# VoltageRegulator.net
KiCad netlist of a schematic drawn in Altium Designer
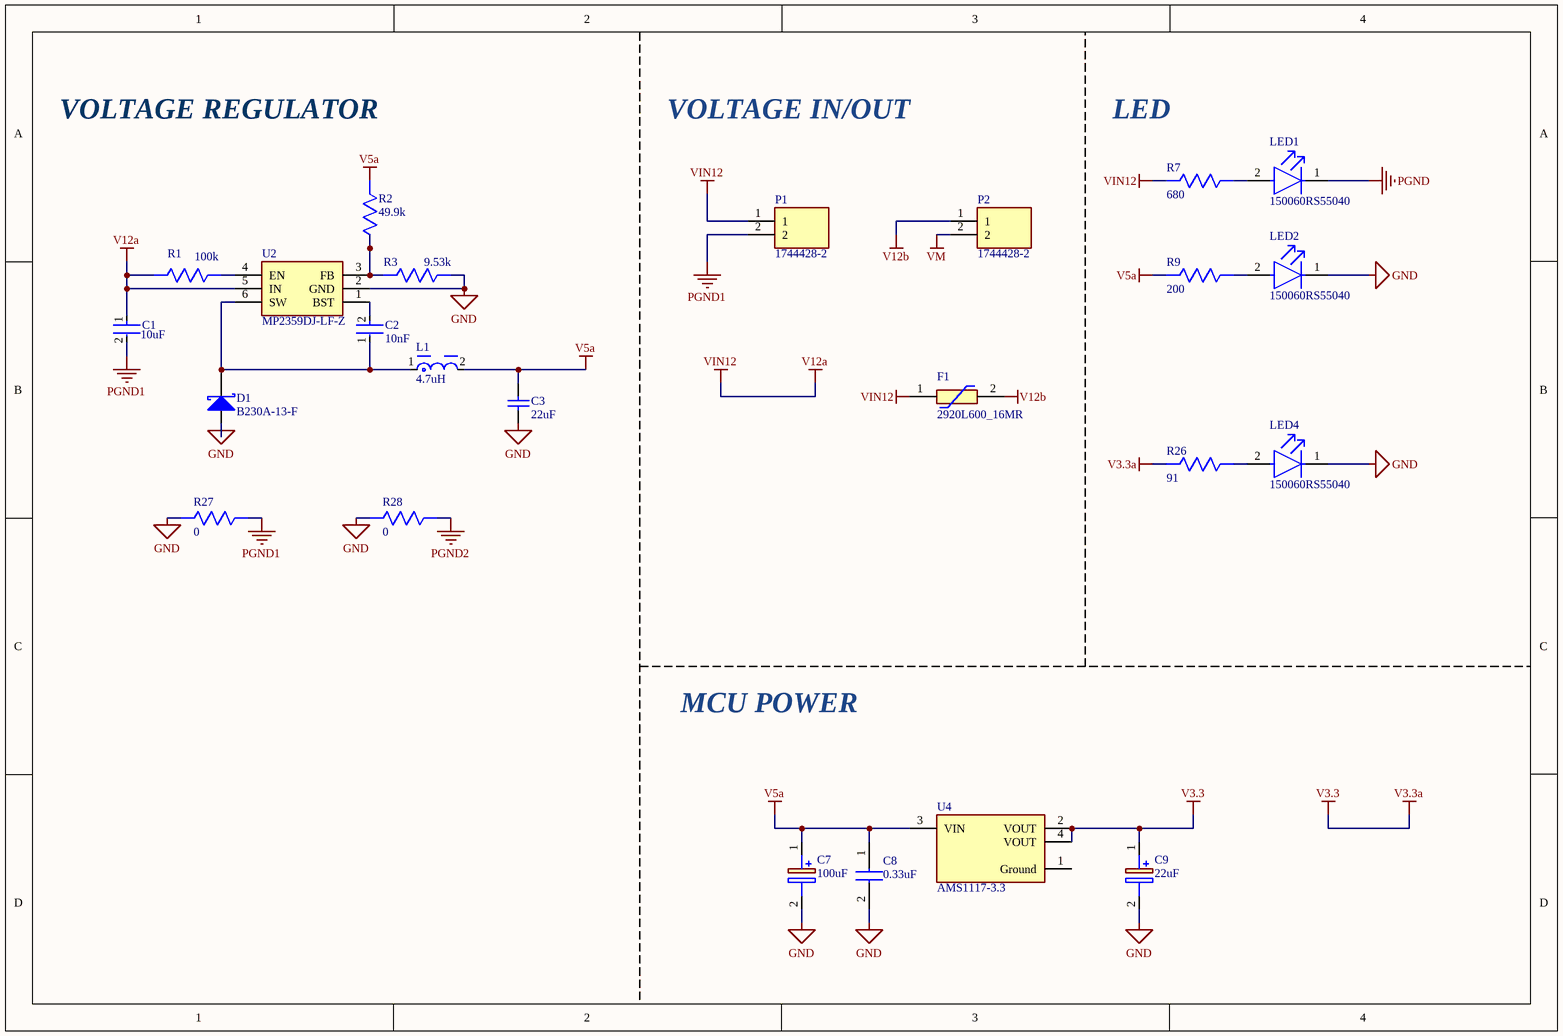
[diagram p0: VoltageRegulator.SchDoc]

(export (version "E")
  (design (tool "Eeschema 10.0.6"))
  (components
    (comp (ref "C1")
      (value "10uF")
      (footprint "FP-C1608-080-IPC_A")
      (description "CAP CER 10UF 25V X5R 0603")
      (fields (field (name "TOLERANCE") "20%"))
      (libsource (lib "Altium Content Vault") (part "11868f565c42a9108669ba33697ecf6"))
    )
    (comp (ref "C2")
      (value "10nF")
      (footprint "FP-C1608-080-0_1-MFG")
      (description "Multilayer Ceramic Capacitors 10nF ±20% 50V X5R SMD 0603")
      (fields (field (name "TOLERANCE") "20%"))
      (libsource (lib "Altium Content Vault") (part "236180d848d6139a670b325ea6854c9"))
    )
    (comp (ref "C3")
      (value "22uF")
      (footprint "CAPC1608X100X20ML10")
      (description "Chip Capacitor, 22 uF, +/- 20%, 10 V, -55 to 85 degC, 0603 (1608 Metric), RoHS, Tape and Reel")
      (fields (field (name "MANUFACTURER") "TDK") (field (name "TOLERANCE") "±20%"))
      (libsource (lib "Altium Content Vault") (part "CAP-NP-2"))
    )
    (comp (ref "C7")
      (value "100uF")
      (footprint "SamacSys:T495E")
      (description "Capacitor Polarised")
      (fields
        (field (name "MANUFACTURER_PART_NUMBER") "T495E107K025ATE100")
        (field (name "MOUSER PART NUMBER") "80-T495E107K025")
      )
      (libsource (lib "*") (part "T495E107K025ATE100"))
    )
    (comp (ref "C8")
      (value "0.33uF")
      (footprint "SamacSys:C1608_Commercial")
      (description "Capacitor")
      (fields
        (field (name "MANUFACTURER_PART_NUMBER") "C1608X7R1H334K080AC")
        (field (name "MOUSER PART NUMBER") "810-C1608X7R1H334K")
      )
      (libsource (lib "*") (part "C1608X7R1H334K080AC"))
    )
    (comp (ref "C9")
      (value "22uF")
      (footprint "SamacSys:T495C")
      (description "Capacitor Polarised")
      (fields
        (field (name "MANUFACTURER_PART_NUMBER") "T495C226K025ATE300")
        (field (name "MOUSER PART NUMBER") "80-T495C226K25E300")
      )
      (libsource (lib "*") (part "T495C226K025ATE300"))
    )
    (comp (ref "D1")
      (value "B230A-13-F")
      (footprint "DIOD-SMA-2_V")
      (fields (field (name "MANUFACTURER") "Diodes Inc"))
      (libsource (lib "Altium Content Vault") (part "DIOD-DSKY-A1K2-2"))
    )
    (comp (ref "F1")
      (value "2920L600_16MR")
      (footprint "SamacSys:FUSC7451X160N")
      (description "Resettable Fuse")
      (fields (field (name "MANUFACTURER_PART_NUMBER") "2920L600/16MR"))
      (libsource (lib "*") (part "2920L600_16MR"))
    )
    (comp (ref "L1")
      (value "4.7uH")
      (footprint "FP-7440530047-MFG")
      (description "FIXED IND 4.7UH 2.4A 38 MOHM SMD")
      (fields (field (name "TOLERANCE") "30%"))
      (libsource (lib "Altium Content Vault") (part "0246fd16f531970cd07674657a1d6aa"))
    )
    (comp (ref "LED1")
      (value "150060RS55040")
      (footprint "FP-150060RS55040-MFG")
      (description "LED RED DIFFUSED 0603 SMD")
      (libsource (lib "Altium Content Vault") (part "8706943c75ba83719d021d2fdc84c58"))
    )
    (comp (ref "LED2")
      (value "150060RS55040")
      (footprint "FP-150060RS55040-MFG")
      (description "LED RED DIFFUSED 0603 SMD")
      (libsource (lib "Altium Content Vault") (part "8706943c75ba83719d021d2fdc84c58"))
    )
    (comp (ref "LED4")
      (value "150060RS55040")
      (footprint "FP-150060RS55040-MFG")
      (description "LED RED DIFFUSED 0603 SMD")
      (libsource (lib "Altium Content Vault") (part "8706943c75ba83719d021d2fdc84c58"))
    )
    (comp (ref "P1")
      (value "1744428-2")
      (footprint "SamacSys:17444282")
      (description "Connector")
      (fields (field (name "MOUSER PART NUMBER") "571-1744428-2"))
      (libsource (lib "SamacSys") (part "1744428-2"))
    )
    (comp (ref "P2")
      (value "1744428-2")
      (footprint "SamacSys:17444282")
      (description "Connector")
      (fields (field (name "MOUSER PART NUMBER") "571-1744428-2"))
      (libsource (lib "SamacSys") (part "1744428-2"))
    )
    (comp (ref "R1")
      (value "100k")
      (footprint "SamacSys:RESC1608X55N")
      (description "Resistor")
      (fields (field (name "MANUFACTURER_PART_NUMBER") "CMP0603-FX-1003ELF"))
      (libsource (lib "SamacSys") (part "CMP0603-FX-1003ELF"))
    )
    (comp (ref "R2")
      (value "49.9k")
      (footprint "SamacSys:RESC1608X55N")
      (description "Resistor")
      (fields (field (name "MANUFACTURER_PART_NUMBER") "CMP0603-FX-1003ELF"))
      (libsource (lib "SamacSys") (part "CMP0603-FX-1003ELF"))
    )
    (comp (ref "R3")
      (value "9.53k")
      (footprint "SamacSys:RESC1608X55N")
      (description "Resistor")
      (fields (field (name "MANUFACTURER_PART_NUMBER") "CMP0603-FX-1003ELF"))
      (libsource (lib "SamacSys") (part "CMP0603-FX-1003ELF"))
    )
    (comp (ref "R7")
      (value "680")
      (footprint "SamacSys:RESC1608X55N")
      (description "Resistor")
      (fields (field (name "MANUFACTURER_PART_NUMBER") "CMP0603-FX-1003ELF"))
      (libsource (lib "SamacSys") (part "CMP0603-FX-1003ELF"))
    )
    (comp (ref "R9")
      (value "200")
      (footprint "SamacSys:RESC1608X55N")
      (description "Resistor")
      (fields (field (name "MANUFACTURER_PART_NUMBER") "CMP0603-FX-1003ELF"))
      (libsource (lib "SamacSys") (part "CMP0603-FX-1003ELF"))
    )
    (comp (ref "R26")
      (value "91")
      (footprint "SamacSys:RESC1608X55N")
      (description "Resistor")
      (fields (field (name "MANUFACTURER_PART_NUMBER") "CMP0603-FX-1003ELF"))
      (libsource (lib "SamacSys") (part "CMP0603-FX-1003ELF"))
    )
    (comp (ref "R27")
      (value "0")
      (footprint "SamacSys:RESC1608X55N")
      (description "Resistor")
      (fields (field (name "MANUFACTURER_PART_NUMBER") "CMP0603-FX-1003ELF"))
      (libsource (lib "SamacSys") (part "CMP0603-FX-1003ELF"))
    )
    (comp (ref "R28")
      (value "0")
      (footprint "SamacSys:RESC1608X55N")
      (description "Resistor")
      (fields (field (name "MANUFACTURER_PART_NUMBER") "CMP0603-FX-1003ELF"))
      (libsource (lib "SamacSys") (part "CMP0603-FX-1003ELF"))
    )
    (comp (ref "U2")
      (value "MP2359DJ-LF-Z")
      (footprint "SamacSys:SOT95P280X100-6N")
      (description "Integrated Circuit")
      (fields (field (name "MOUSER2 PART NUMBER") "946-MP2359DJLFZ"))
      (libsource (lib "*") (part "MP2359DJ-LF-Z"))
    )
    (comp (ref "U4")
      (value "AMS1117-3.3")
      (footprint "FP-AMS1117-IPC_C")
      (description "LDO Voltage Regulators 1A, 3.3V")
      (fields
        (field (name "OCTOPART") "https://octopart.com/ams1117-3.3-advanced+monolithic+systems-25899300")
        (field (name "MANUFACTURER") "Advanced Monolithic Systems")
      )
      (libsource (lib "Altium Content Vault") (part "8bdbb5f8e77002000e30dd2845d0354"))
    )
  )
  (nets
    (net (code "1") (name "GND") (class "Default")
      (node (ref "C3") (pin "1") (pinfunction "1_1") (pintype "passive"))
      (node (ref "C7") (pin "2") (pinfunction "-_2") (pintype "passive"))
      (node (ref "C8") (pin "2") (pinfunction "2_2") (pintype "passive"))
      (node (ref "C9") (pin "2") (pinfunction "-_2") (pintype "passive"))
      (node (ref "D1") (pin "1") (pinfunction "A_1") (pintype "passive"))
      (node (ref "LED2") (pin "1") (pinfunction "C_1") (pintype "passive"))
      (node (ref "LED4") (pin "1") (pinfunction "C_1") (pintype "passive"))
      (node (ref "R27") (pin "1") (pinfunction "1_1") (pintype "passive"))
      (node (ref "R28") (pin "1") (pinfunction "1_1") (pintype "passive"))
      (node (ref "R3") (pin "2") (pinfunction "2_2") (pintype "passive"))
      (node (ref "U2") (pin "2") (pinfunction "GND_2") (pintype "passive"))
    )
    (net (code "2") (name "Net-(D1-K)") (class "Default")
      (node (ref "C2") (pin "1") (pinfunction "1_1") (pintype "passive"))
      (node (ref "D1") (pin "2") (pinfunction "K_2") (pintype "passive"))
      (node (ref "L1") (pin "1") (pinfunction "1_1") (pintype "passive"))
      (node (ref "U2") (pin "6") (pinfunction "SW_6") (pintype "passive"))
    )
    (net (code "3") (name "Net-(LED1-A)") (class "Default")
      (node (ref "LED1") (pin "2") (pinfunction "A_2") (pintype "passive"))
      (node (ref "R7") (pin "2") (pinfunction "2_2") (pintype "passive"))
    )
    (net (code "4") (name "Net-(LED2-A)") (class "Default")
      (node (ref "LED2") (pin "2") (pinfunction "A_2") (pintype "passive"))
      (node (ref "R9") (pin "2") (pinfunction "2_2") (pintype "passive"))
    )
    (net (code "5") (name "Net-(LED4-A)") (class "Default")
      (node (ref "LED4") (pin "2") (pinfunction "A_2") (pintype "passive"))
      (node (ref "R26") (pin "2") (pinfunction "2_2") (pintype "passive"))
    )
    (net (code "6") (name "Net-(U2-BST)") (class "Default")
      (node (ref "C2") (pin "2") (pinfunction "2_2") (pintype "passive"))
      (node (ref "U2") (pin "1") (pinfunction "BST_1") (pintype "passive"))
    )
    (net (code "7") (name "Net-(U2-EN)") (class "Default")
      (node (ref "R1") (pin "2") (pinfunction "2_2") (pintype "passive"))
      (node (ref "U2") (pin "4") (pinfunction "EN_4") (pintype "passive"))
    )
    (net (code "8") (name "Net-(U2-FB)") (class "Default")
      (node (ref "R2") (pin "2") (pinfunction "2_2") (pintype "passive"))
      (node (ref "R3") (pin "1") (pinfunction "1_1") (pintype "passive"))
      (node (ref "U2") (pin "3") (pinfunction "FB_3") (pintype "passive"))
    )
    (net (code "9") (name "PGND") (class "Default")
      (node (ref "LED1") (pin "1") (pinfunction "C_1") (pintype "passive"))
    )
    (net (code "10") (name "PGND1") (class "Default")
      (node (ref "C1") (pin "2") (pinfunction "2_2") (pintype "passive"))
      (node (ref "P1") (pin "2") (pinfunction "2_2") (pintype "passive"))
      (node (ref "R27") (pin "2") (pinfunction "2_2") (pintype "passive"))
    )
    (net (code "11") (name "PGND2") (class "Default")
      (node (ref "R28") (pin "2") (pinfunction "2_2") (pintype "passive"))
    )
    (net (code "12") (name "V3.3") (class "Default")
      (node (ref "C9") (pin "1") (pinfunction "+_1") (pintype "passive"))
      (node (ref "R26") (pin "1") (pinfunction "1_1") (pintype "passive"))
      (node (ref "U4") (pin "2") (pinfunction "VOUT_2") (pintype "passive"))
      (node (ref "U4") (pin "4") (pinfunction "VOUT_4") (pintype "passive"))
    )
    (net (code "13") (name "V5a") (class "Default")
      (node (ref "C3") (pin "2") (pinfunction "2_2") (pintype "passive"))
      (node (ref "C7") (pin "1") (pinfunction "+_1") (pintype "passive"))
      (node (ref "C8") (pin "1") (pinfunction "1_1") (pintype "passive"))
      (node (ref "L1") (pin "2") (pinfunction "2_2") (pintype "passive"))
      (node (ref "R2") (pin "1") (pinfunction "1_1") (pintype "passive"))
      (node (ref "R9") (pin "1") (pinfunction "1_1") (pintype "passive"))
      (node (ref "U4") (pin "3") (pinfunction "VIN_3") (pintype "power_in"))
    )
    (net (code "14") (name "V12a") (class "Default")
      (node (ref "C1") (pin "1") (pinfunction "1_1") (pintype "passive"))
      (node (ref "F1") (pin "1") (pinfunction "1_1") (pintype "passive"))
      (node (ref "P1") (pin "1") (pinfunction "1_1") (pintype "passive"))
      (node (ref "R1") (pin "1") (pinfunction "1_1") (pintype "passive"))
      (node (ref "R7") (pin "1") (pinfunction "1_1") (pintype "passive"))
      (node (ref "U2") (pin "5") (pinfunction "IN_5") (pintype "passive"))
    )
    (net (code "15") (name "V12b") (class "Default")
      (node (ref "F1") (pin "2") (pinfunction "2_2") (pintype "passive"))
      (node (ref "P2") (pin "1") (pinfunction "1_1") (pintype "passive"))
    )
    (net (code "16") (name "VM") (class "Default")
      (node (ref "P2") (pin "2") (pinfunction "2_2") (pintype "passive"))
    )
    (net (code "17") (name "unconnected-(U4-Ground-Pad1)") (class "Default")
      (node (ref "U4") (pin "1") (pinfunction "Ground_1") (pintype "power_in"))
    )
  )
)
